# test_usb_hub.net
KiCad netlist of a schematic drawn in EAGLE
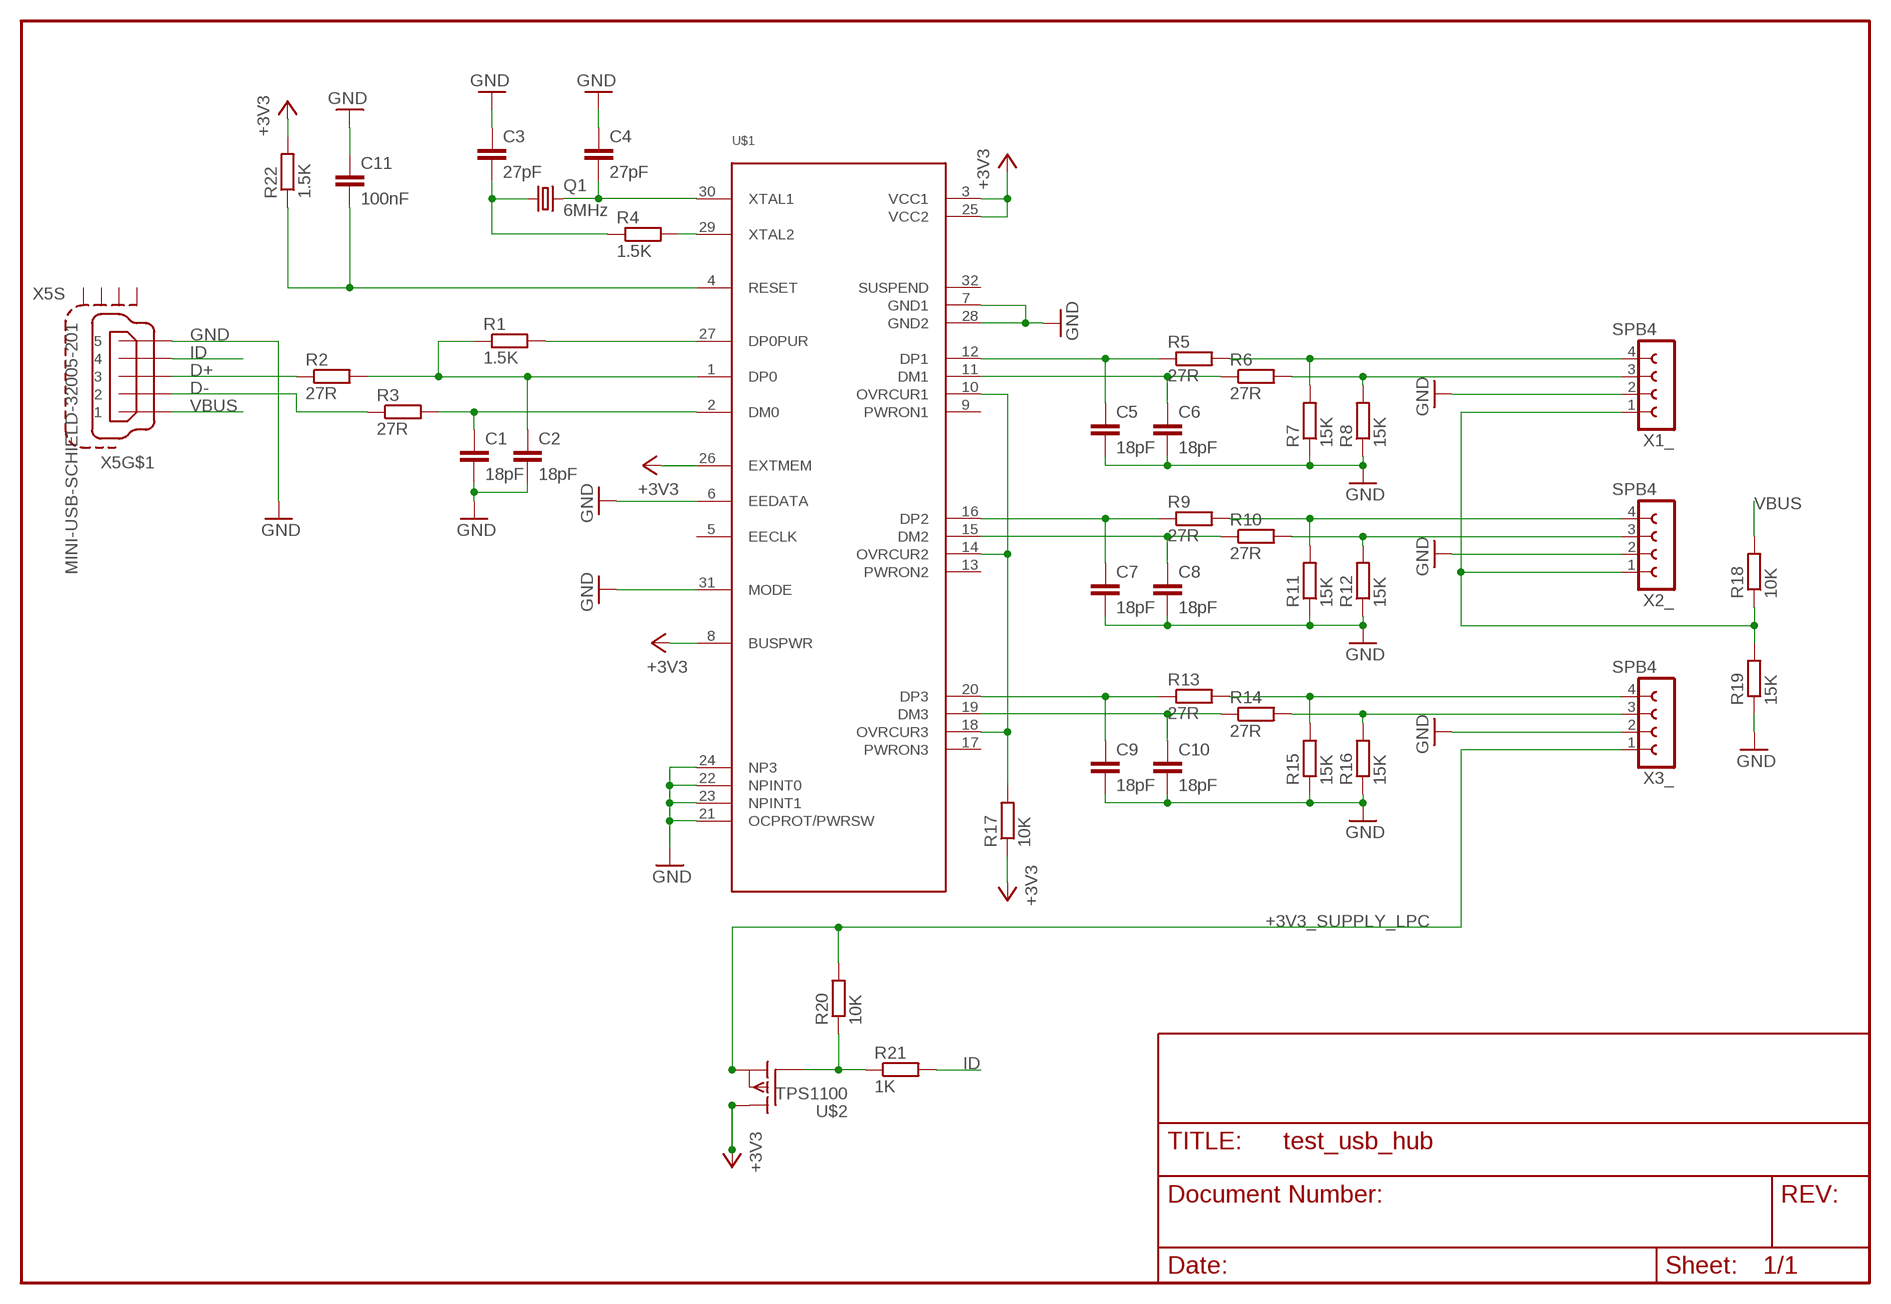
[diagram p0: schematic, sheet 1]

(export (version "E")
  (design (tool "Eeschema 10.0.6"))
  (components
    (comp (ref "C1")
      (value "18pF")
      (footprint "eagle-import:C1206")
      (libsource (lib "eagle-import") (part "C-EUC1206"))
    )
    (comp (ref "C2")
      (value "18pF")
      (footprint "eagle-import:C1206")
      (libsource (lib "eagle-import") (part "C-EUC1206"))
    )
    (comp (ref "C3")
      (value "27pF")
      (footprint "eagle-import:C1206")
      (libsource (lib "eagle-import") (part "C-EUC1206"))
    )
    (comp (ref "C4")
      (value "27pF")
      (footprint "eagle-import:C1206")
      (libsource (lib "eagle-import") (part "C-EUC1206"))
    )
    (comp (ref "C5")
      (value "18pF")
      (footprint "eagle-import:C1206")
      (libsource (lib "eagle-import") (part "C-EUC1206"))
    )
    (comp (ref "C6")
      (value "18pF")
      (footprint "eagle-import:C1206")
      (libsource (lib "eagle-import") (part "C-EUC1206"))
    )
    (comp (ref "C7")
      (value "18pF")
      (footprint "eagle-import:C1206")
      (libsource (lib "eagle-import") (part "C-EUC1206"))
    )
    (comp (ref "C8")
      (value "18pF")
      (footprint "eagle-import:C1206")
      (libsource (lib "eagle-import") (part "C-EUC1206"))
    )
    (comp (ref "C9")
      (value "18pF")
      (footprint "eagle-import:C1206")
      (libsource (lib "eagle-import") (part "C-EUC1206"))
    )
    (comp (ref "C10")
      (value "18pF")
      (footprint "eagle-import:C1206")
      (libsource (lib "eagle-import") (part "C-EUC1206"))
    )
    (comp (ref "C11")
      (value "100nF")
      (footprint "eagle-import:C1206")
      (libsource (lib "eagle-import") (part "C-EUC1206"))
    )
    (comp (ref "Q1")
      (value "6MHz")
      (footprint "eagle-import:HC49U-V")
      (libsource (lib "eagle-import") (part "CRYTALHC49U-V"))
    )
    (comp (ref "R1")
      (value "1.5K")
      (footprint "eagle-import:R1206")
      (libsource (lib "eagle-import") (part "R-EU_R1206"))
    )
    (comp (ref "R2")
      (value "27R")
      (footprint "eagle-import:R1206")
      (libsource (lib "eagle-import") (part "R-EU_R1206"))
    )
    (comp (ref "R3")
      (value "27R")
      (footprint "eagle-import:R1206")
      (libsource (lib "eagle-import") (part "R-EU_R1206"))
    )
    (comp (ref "R4")
      (value "1.5K")
      (footprint "eagle-import:R1206")
      (libsource (lib "eagle-import") (part "R-EU_R1206"))
    )
    (comp (ref "R5")
      (value "27R")
      (footprint "eagle-import:R1206")
      (libsource (lib "eagle-import") (part "R-EU_R1206"))
    )
    (comp (ref "R6")
      (value "27R")
      (footprint "eagle-import:R1206")
      (libsource (lib "eagle-import") (part "R-EU_R1206"))
    )
    (comp (ref "R7")
      (value "15K")
      (footprint "eagle-import:R1206")
      (libsource (lib "eagle-import") (part "R-EU_R1206"))
    )
    (comp (ref "R8")
      (value "15K")
      (footprint "eagle-import:R1206")
      (libsource (lib "eagle-import") (part "R-EU_R1206"))
    )
    (comp (ref "R9")
      (value "27R")
      (footprint "eagle-import:R1206")
      (libsource (lib "eagle-import") (part "R-EU_R1206"))
    )
    (comp (ref "R10")
      (value "27R")
      (footprint "eagle-import:R1206")
      (libsource (lib "eagle-import") (part "R-EU_R1206"))
    )
    (comp (ref "R11")
      (value "15K")
      (footprint "eagle-import:R1206")
      (libsource (lib "eagle-import") (part "R-EU_R1206"))
    )
    (comp (ref "R12")
      (value "15K")
      (footprint "eagle-import:R1206")
      (libsource (lib "eagle-import") (part "R-EU_R1206"))
    )
    (comp (ref "R13")
      (value "27R")
      (footprint "eagle-import:R1206")
      (libsource (lib "eagle-import") (part "R-EU_R1206"))
    )
    (comp (ref "R14")
      (value "27R")
      (footprint "eagle-import:R1206")
      (libsource (lib "eagle-import") (part "R-EU_R1206"))
    )
    (comp (ref "R15")
      (value "15K")
      (footprint "eagle-import:R1206")
      (libsource (lib "eagle-import") (part "R-EU_R1206"))
    )
    (comp (ref "R16")
      (value "15K")
      (footprint "eagle-import:R1206")
      (libsource (lib "eagle-import") (part "R-EU_R1206"))
    )
    (comp (ref "R17")
      (value "10K")
      (footprint "eagle-import:R1206")
      (libsource (lib "eagle-import") (part "R-EU_R1206"))
    )
    (comp (ref "R18")
      (value "10K")
      (footprint "eagle-import:R1206")
      (libsource (lib "eagle-import") (part "R-EU_R1206"))
    )
    (comp (ref "R19")
      (value "15K")
      (footprint "eagle-import:R1206")
      (libsource (lib "eagle-import") (part "R-EU_R1206"))
    )
    (comp (ref "R20")
      (value "10K")
      (footprint "eagle-import:R1206")
      (libsource (lib "eagle-import") (part "R-EU_R1206"))
    )
    (comp (ref "R21")
      (value "1K")
      (footprint "eagle-import:R1206")
      (libsource (lib "eagle-import") (part "R-EU_R1206"))
    )
    (comp (ref "R22")
      (value "1.5K")
      (footprint "eagle-import:R1206")
      (libsource (lib "eagle-import") (part "R-EU_R1206"))
    )
    (comp (ref "U$1")
      (value "TUSB2036OK")
      (footprint "eagle-import:QFP-32")
      (libsource (lib "eagle-import") (part "TUSB2036OK"))
    )
    (comp (ref "U$2")
      (value "TPS1100")
      (footprint "eagle-import:SOIC8")
      (libsource (lib "eagle-import") (part "TPS1100"))
    )
    (comp (ref "X1_")
      (value "SPB4")
      (footprint "eagle-import:SPB4")
      (libsource (lib "eagle-import") (part "SPB4"))
    )
    (comp (ref "X2_")
      (value "SPB4")
      (footprint "eagle-import:SPB4")
      (libsource (lib "eagle-import") (part "SPB4"))
    )
    (comp (ref "X3_")
      (value "SPB4")
      (footprint "eagle-import:SPB4")
      (libsource (lib "eagle-import") (part "SPB4"))
    )
    (comp (ref "X5")
      (value "MINI-USB-SCHIELD-32005-201")
      (footprint "eagle-import:32005-201")
      (libsource (lib "eagle-import") (part "MINI-USB-SCHIELD-32005-201"))
    )
  )
  (nets
    (net (code "1") (name "+3V3") (class "Default")
      (node (ref "R17") (pin "1") (pinfunction "1_1") (pintype "passive"))
      (node (ref "R22") (pin "2") (pinfunction "2_2") (pintype "passive"))
      (node (ref "U$1") (pin "25") (pinfunction "VCC2_25") (pintype "bidirectional"))
      (node (ref "U$1") (pin "26") (pinfunction "EXTMEM_26") (pintype "bidirectional"))
      (node (ref "U$1") (pin "3") (pinfunction "VCC1_3") (pintype "bidirectional"))
      (node (ref "U$1") (pin "8") (pinfunction "BUSPWR_8") (pintype "bidirectional"))
      (node (ref "U$2") (pin "5") (pinfunction "D_5") (pintype "passive"))
      (node (ref "U$2") (pin "6") (pinfunction "D1_6") (pintype "passive"))
      (node (ref "U$2") (pin "7") (pinfunction "D2_7") (pintype "passive"))
      (node (ref "U$2") (pin "8") (pinfunction "D3_8") (pintype "passive"))
    )
    (net (code "2") (name "/+3V3_SUPPLY_LPC") (class "Default")
      (node (ref "R20") (pin "2") (pinfunction "2_2") (pintype "passive"))
      (node (ref "U$2") (pin "1") (pinfunction "S_1") (pintype "passive"))
      (node (ref "U$2") (pin "2") (pinfunction "S1_2") (pintype "passive"))
      (node (ref "U$2") (pin "3") (pinfunction "S2_3") (pintype "passive"))
      (node (ref "X3_") (pin "1") (pinfunction "1_1") (pintype "passive"))
    )
    (net (code "3") (name "/D+") (class "Default")
      (node (ref "R2") (pin "1") (pinfunction "1_1") (pintype "passive"))
      (node (ref "X5") (pin "3") (pinfunction "3_3") (pintype "passive"))
    )
    (net (code "4") (name "/D-") (class "Default")
      (node (ref "R3") (pin "1") (pinfunction "1_1") (pintype "passive"))
      (node (ref "X5") (pin "2") (pinfunction "2_2") (pintype "passive"))
    )
    (net (code "5") (name "/ID") (class "Default")
      (node (ref "R21") (pin "2") (pinfunction "2_2") (pintype "passive"))
      (node (ref "X5") (pin "4") (pinfunction "4_4") (pintype "passive"))
    )
    (net (code "6") (name "/VBUS") (class "Default")
      (node (ref "R18") (pin "2") (pinfunction "2_2") (pintype "passive"))
      (node (ref "X5") (pin "1") (pinfunction "1_1") (pintype "passive"))
    )
    (net (code "7") (name "GND") (class "Default")
      (node (ref "C1") (pin "2") (pinfunction "2_2") (pintype "passive"))
      (node (ref "C10") (pin "2") (pinfunction "2_2") (pintype "passive"))
      (node (ref "C11") (pin "1") (pinfunction "1_1") (pintype "passive"))
      (node (ref "C2") (pin "2") (pinfunction "2_2") (pintype "passive"))
      (node (ref "C3") (pin "1") (pinfunction "1_1") (pintype "passive"))
      (node (ref "C4") (pin "1") (pinfunction "1_1") (pintype "passive"))
      (node (ref "C5") (pin "2") (pinfunction "2_2") (pintype "passive"))
      (node (ref "C6") (pin "2") (pinfunction "2_2") (pintype "passive"))
      (node (ref "C7") (pin "2") (pinfunction "2_2") (pintype "passive"))
      (node (ref "C8") (pin "2") (pinfunction "2_2") (pintype "passive"))
      (node (ref "C9") (pin "2") (pinfunction "2_2") (pintype "passive"))
      (node (ref "R11") (pin "1") (pinfunction "1_1") (pintype "passive"))
      (node (ref "R12") (pin "1") (pinfunction "1_1") (pintype "passive"))
      (node (ref "R15") (pin "1") (pinfunction "1_1") (pintype "passive"))
      (node (ref "R16") (pin "1") (pinfunction "1_1") (pintype "passive"))
      (node (ref "R19") (pin "1") (pinfunction "1_1") (pintype "passive"))
      (node (ref "R7") (pin "1") (pinfunction "1_1") (pintype "passive"))
      (node (ref "R8") (pin "1") (pinfunction "1_1") (pintype "passive"))
      (node (ref "U$1") (pin "21") (pinfunction "OCPROT/PWRSW_21") (pintype "bidirectional"))
      (node (ref "U$1") (pin "22") (pinfunction "NPINT0_22") (pintype "bidirectional"))
      (node (ref "U$1") (pin "23") (pinfunction "NPINT1_23") (pintype "bidirectional"))
      (node (ref "U$1") (pin "24") (pinfunction "NP3_24") (pintype "bidirectional"))
      (node (ref "U$1") (pin "28") (pinfunction "GND2_28") (pintype "bidirectional"))
      (node (ref "U$1") (pin "31") (pinfunction "MODE_31") (pintype "bidirectional"))
      (node (ref "U$1") (pin "6") (pinfunction "EEDATA_6") (pintype "bidirectional"))
      (node (ref "U$1") (pin "7") (pinfunction "GND1_7") (pintype "bidirectional"))
      (node (ref "X1_") (pin "2") (pinfunction "2_2") (pintype "passive"))
      (node (ref "X2_") (pin "2") (pinfunction "2_2") (pintype "passive"))
      (node (ref "X3_") (pin "2") (pinfunction "2_2") (pintype "passive"))
      (node (ref "X5") (pin "5") (pinfunction "5_5") (pintype "passive"))
    )
    (net (code "8") (name "Net-(C3-Pad2)") (class "Default")
      (node (ref "C3") (pin "2") (pinfunction "2_2") (pintype "passive"))
      (node (ref "Q1") (pin "1") (pinfunction "1_1") (pintype "passive"))
      (node (ref "R4") (pin "1") (pinfunction "1_1") (pintype "passive"))
    )
    (net (code "9") (name "Net-(R5-Pad2)") (class "Default")
      (node (ref "R5") (pin "2") (pinfunction "2_2") (pintype "passive"))
      (node (ref "R7") (pin "2") (pinfunction "2_2") (pintype "passive"))
      (node (ref "X1_") (pin "4") (pinfunction "4_4") (pintype "passive"))
    )
    (net (code "10") (name "Net-(R6-Pad2)") (class "Default")
      (node (ref "R6") (pin "2") (pinfunction "2_2") (pintype "passive"))
      (node (ref "R8") (pin "2") (pinfunction "2_2") (pintype "passive"))
      (node (ref "X1_") (pin "3") (pinfunction "3_3") (pintype "passive"))
    )
    (net (code "11") (name "Net-(R10-Pad2)") (class "Default")
      (node (ref "R10") (pin "2") (pinfunction "2_2") (pintype "passive"))
      (node (ref "R12") (pin "2") (pinfunction "2_2") (pintype "passive"))
      (node (ref "X2_") (pin "3") (pinfunction "3_3") (pintype "passive"))
    )
    (net (code "12") (name "Net-(R11-Pad2)") (class "Default")
      (node (ref "R11") (pin "2") (pinfunction "2_2") (pintype "passive"))
      (node (ref "R9") (pin "2") (pinfunction "2_2") (pintype "passive"))
      (node (ref "X2_") (pin "4") (pinfunction "4_4") (pintype "passive"))
    )
    (net (code "13") (name "Net-(R13-Pad2)") (class "Default")
      (node (ref "R13") (pin "2") (pinfunction "2_2") (pintype "passive"))
      (node (ref "R15") (pin "2") (pinfunction "2_2") (pintype "passive"))
      (node (ref "X3_") (pin "4") (pinfunction "4_4") (pintype "passive"))
    )
    (net (code "14") (name "Net-(R14-Pad2)") (class "Default")
      (node (ref "R14") (pin "2") (pinfunction "2_2") (pintype "passive"))
      (node (ref "R16") (pin "2") (pinfunction "2_2") (pintype "passive"))
      (node (ref "X3_") (pin "3") (pinfunction "3_3") (pintype "passive"))
    )
    (net (code "15") (name "Net-(R18-Pad1)") (class "Default")
      (node (ref "R18") (pin "1") (pinfunction "1_1") (pintype "passive"))
      (node (ref "R19") (pin "2") (pinfunction "2_2") (pintype "passive"))
      (node (ref "X1_") (pin "1") (pinfunction "1_1") (pintype "passive"))
      (node (ref "X2_") (pin "1") (pinfunction "1_1") (pintype "passive"))
    )
    (net (code "16") (name "Net-(U$1-DM0)") (class "Default")
      (node (ref "C1") (pin "1") (pinfunction "1_1") (pintype "passive"))
      (node (ref "R3") (pin "2") (pinfunction "2_2") (pintype "passive"))
      (node (ref "U$1") (pin "2") (pinfunction "DM0_2") (pintype "bidirectional"))
    )
    (net (code "17") (name "Net-(U$1-DM1)") (class "Default")
      (node (ref "C6") (pin "1") (pinfunction "1_1") (pintype "passive"))
      (node (ref "R6") (pin "1") (pinfunction "1_1") (pintype "passive"))
      (node (ref "U$1") (pin "11") (pinfunction "DM1_11") (pintype "bidirectional"))
    )
    (net (code "18") (name "Net-(U$1-DM2)") (class "Default")
      (node (ref "C8") (pin "1") (pinfunction "1_1") (pintype "passive"))
      (node (ref "R10") (pin "1") (pinfunction "1_1") (pintype "passive"))
      (node (ref "U$1") (pin "15") (pinfunction "DM2_15") (pintype "bidirectional"))
    )
    (net (code "19") (name "Net-(U$1-DM3)") (class "Default")
      (node (ref "C10") (pin "1") (pinfunction "1_1") (pintype "passive"))
      (node (ref "R14") (pin "1") (pinfunction "1_1") (pintype "passive"))
      (node (ref "U$1") (pin "19") (pinfunction "DM3_19") (pintype "bidirectional"))
    )
    (net (code "20") (name "Net-(U$1-DP0)") (class "Default")
      (node (ref "C2") (pin "1") (pinfunction "1_1") (pintype "passive"))
      (node (ref "R1") (pin "1") (pinfunction "1_1") (pintype "passive"))
      (node (ref "R2") (pin "2") (pinfunction "2_2") (pintype "passive"))
      (node (ref "U$1") (pin "1") (pinfunction "DP0_1") (pintype "bidirectional"))
    )
    (net (code "21") (name "Net-(U$1-DP0PUR)") (class "Default")
      (node (ref "R1") (pin "2") (pinfunction "2_2") (pintype "passive"))
      (node (ref "U$1") (pin "27") (pinfunction "DP0PUR_27") (pintype "bidirectional"))
    )
    (net (code "22") (name "Net-(U$1-DP1)") (class "Default")
      (node (ref "C5") (pin "1") (pinfunction "1_1") (pintype "passive"))
      (node (ref "R5") (pin "1") (pinfunction "1_1") (pintype "passive"))
      (node (ref "U$1") (pin "12") (pinfunction "DP1_12") (pintype "bidirectional"))
    )
    (net (code "23") (name "Net-(U$1-DP2)") (class "Default")
      (node (ref "C7") (pin "1") (pinfunction "1_1") (pintype "passive"))
      (node (ref "R9") (pin "1") (pinfunction "1_1") (pintype "passive"))
      (node (ref "U$1") (pin "16") (pinfunction "DP2_16") (pintype "bidirectional"))
    )
    (net (code "24") (name "Net-(U$1-DP3)") (class "Default")
      (node (ref "C9") (pin "1") (pinfunction "1_1") (pintype "passive"))
      (node (ref "R13") (pin "1") (pinfunction "1_1") (pintype "passive"))
      (node (ref "U$1") (pin "20") (pinfunction "DP3_20") (pintype "bidirectional"))
    )
    (net (code "25") (name "Net-(U$1-OVRCUR1)") (class "Default")
      (node (ref "R17") (pin "2") (pinfunction "2_2") (pintype "passive"))
      (node (ref "U$1") (pin "10") (pinfunction "OVRCUR1_10") (pintype "bidirectional"))
      (node (ref "U$1") (pin "14") (pinfunction "OVRCUR2_14") (pintype "bidirectional"))
      (node (ref "U$1") (pin "18") (pinfunction "OVRCUR3_18") (pintype "bidirectional"))
    )
    (net (code "26") (name "Net-(U$1-RESET)") (class "Default")
      (node (ref "C11") (pin "2") (pinfunction "2_2") (pintype "passive"))
      (node (ref "R22") (pin "1") (pinfunction "1_1") (pintype "passive"))
      (node (ref "U$1") (pin "4") (pinfunction "RESET_4") (pintype "bidirectional"))
    )
    (net (code "27") (name "Net-(U$1-XTAL1)") (class "Default")
      (node (ref "C4") (pin "2") (pinfunction "2_2") (pintype "passive"))
      (node (ref "Q1") (pin "2") (pinfunction "2_2") (pintype "passive"))
      (node (ref "U$1") (pin "30") (pinfunction "XTAL1_30") (pintype "bidirectional"))
    )
    (net (code "28") (name "Net-(U$1-XTAL2)") (class "Default")
      (node (ref "R4") (pin "2") (pinfunction "2_2") (pintype "passive"))
      (node (ref "U$1") (pin "29") (pinfunction "XTAL2_29") (pintype "bidirectional"))
    )
    (net (code "29") (name "Net-(U$2-G)") (class "Default")
      (node (ref "R20") (pin "1") (pinfunction "1_1") (pintype "passive"))
      (node (ref "R21") (pin "1") (pinfunction "1_1") (pintype "passive"))
      (node (ref "U$2") (pin "4") (pinfunction "G_4") (pintype "passive"))
    )
    (net (code "30") (name "unconnected-(U$1-EECLK-Pad5)") (class "Default")
      (node (ref "U$1") (pin "5") (pinfunction "EECLK_5") (pintype "bidirectional"))
    )
    (net (code "31") (name "unconnected-(U$1-PWRON1-Pad9)") (class "Default")
      (node (ref "U$1") (pin "9") (pinfunction "PWRON1_9") (pintype "bidirectional"))
    )
    (net (code "32") (name "unconnected-(U$1-PWRON2-Pad13)") (class "Default")
      (node (ref "U$1") (pin "13") (pinfunction "PWRON2_13") (pintype "bidirectional"))
    )
    (net (code "33") (name "unconnected-(U$1-PWRON3-Pad17)") (class "Default")
      (node (ref "U$1") (pin "17") (pinfunction "PWRON3_17") (pintype "bidirectional"))
    )
    (net (code "34") (name "unconnected-(U$1-SUSPEND-Pad32)") (class "Default")
      (node (ref "U$1") (pin "32") (pinfunction "SUSPEND_32") (pintype "bidirectional"))
    )
    (net (code "35") (name "unconnected-(X5B-S1-PadM1)") (class "Default")
      (node (ref "X5") (pin "M1") (pinfunction "S1_M1") (pintype "passive"))
    )
    (net (code "36") (name "unconnected-(X5B-S2-PadM2)") (class "Default")
      (node (ref "X5") (pin "M2") (pinfunction "S2_M2") (pintype "passive"))
    )
    (net (code "37") (name "unconnected-(X5B-S3-PadM3)") (class "Default")
      (node (ref "X5") (pin "M3") (pinfunction "S3_M3") (pintype "passive"))
    )
    (net (code "38") (name "unconnected-(X5B-S4-PadM4)") (class "Default")
      (node (ref "X5") (pin "M4") (pinfunction "S4_M4") (pintype "passive"))
    )
  )
)
